# strip.net
KiCad netlist of a schematic drawn in EAGLE
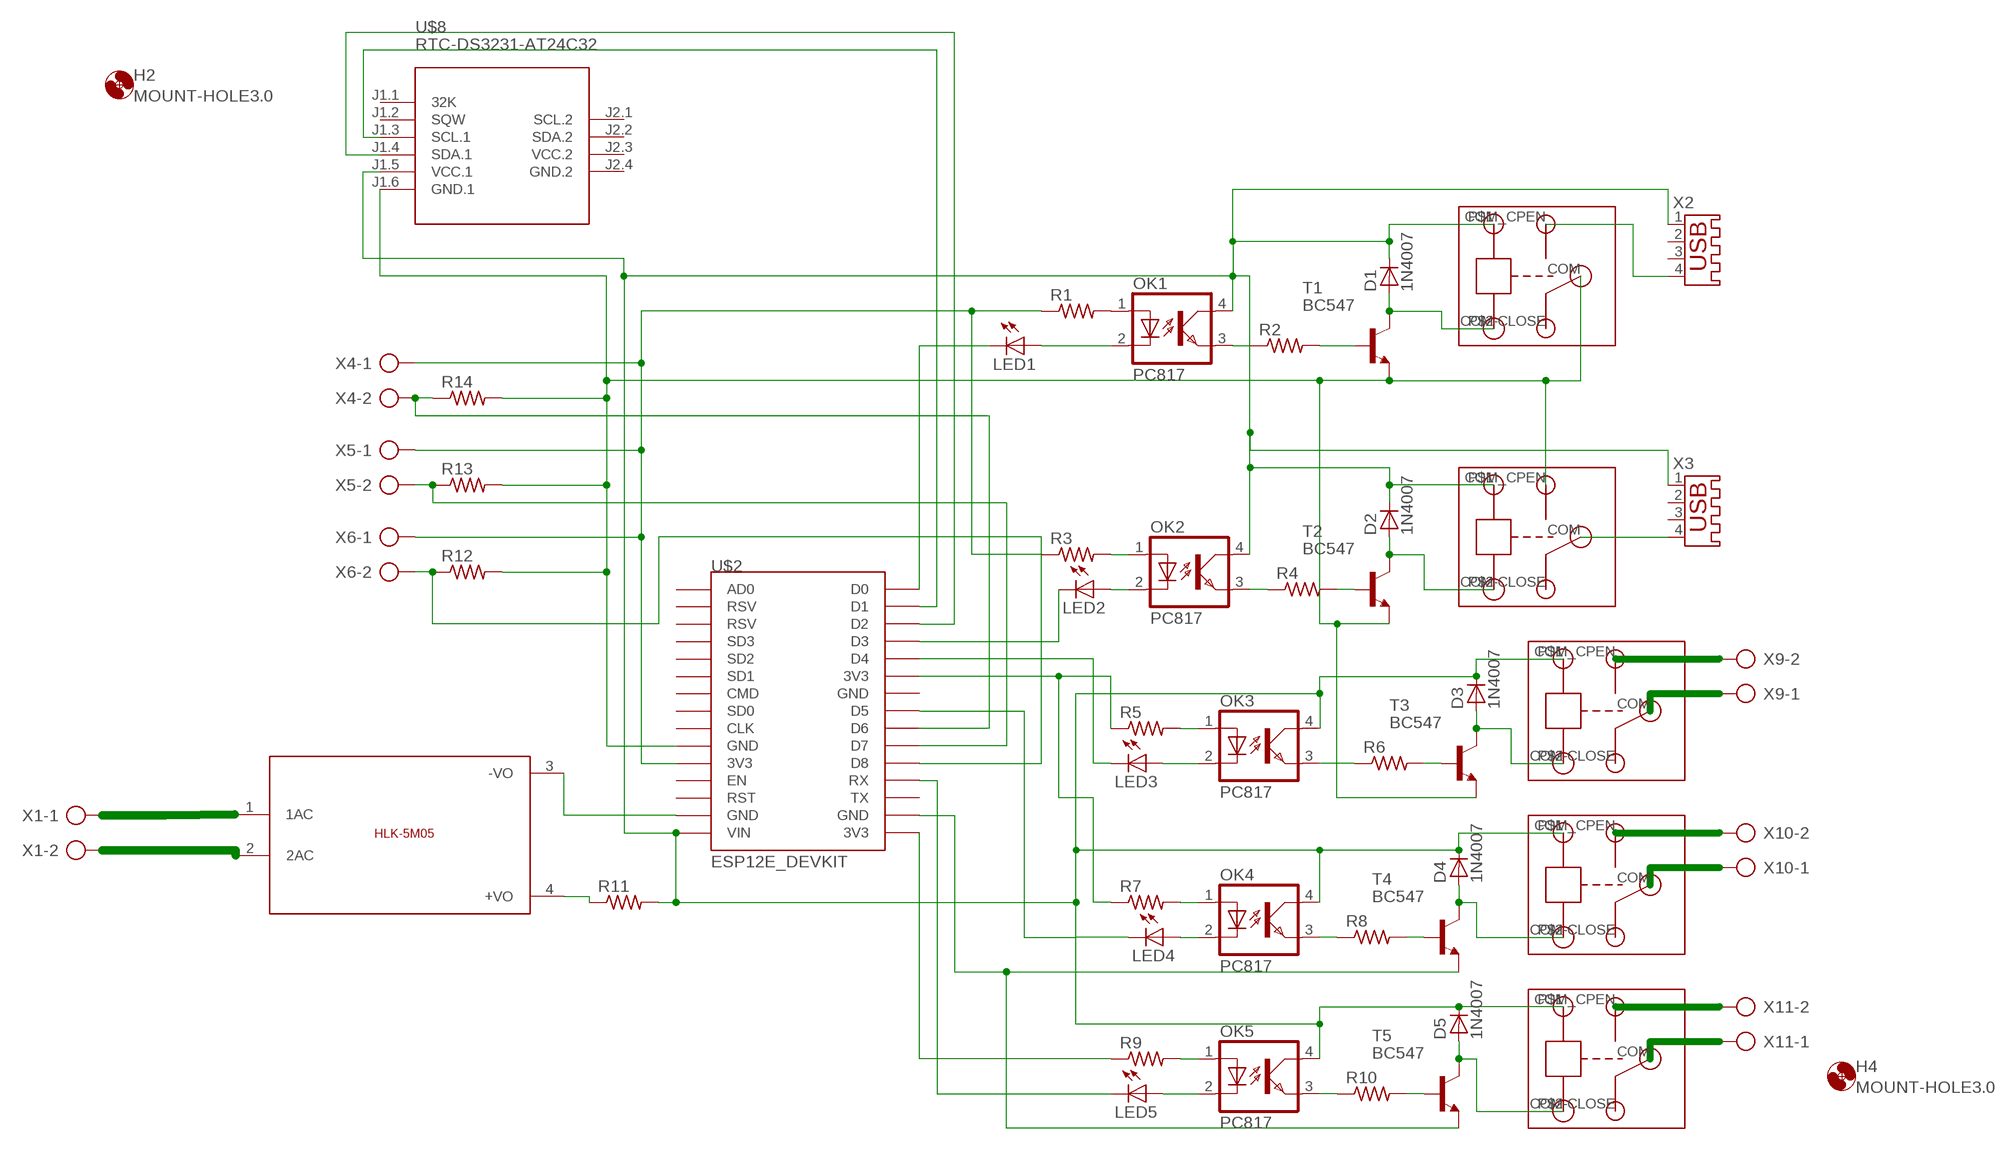
[diagram p0: schematic, sheet 1]

(export (version "E")
  (design (tool "Eeschema 10.0.6"))
  (components
    (comp (ref "D1")
      (value "1N4007")
      (footprint "eagle-import:SMA")
      (libsource (lib "eagle-import") (part "1N4007"))
    )
    (comp (ref "D2")
      (value "1N4007")
      (footprint "eagle-import:SMA")
      (libsource (lib "eagle-import") (part "1N4007"))
    )
    (comp (ref "D3")
      (value "1N4007")
      (footprint "eagle-import:SMA")
      (libsource (lib "eagle-import") (part "1N4007"))
    )
    (comp (ref "D4")
      (value "1N4007")
      (footprint "eagle-import:SMA")
      (libsource (lib "eagle-import") (part "1N4007"))
    )
    (comp (ref "D5")
      (value "1N4007")
      (footprint "eagle-import:SMA")
      (libsource (lib "eagle-import") (part "1N4007"))
    )
    (comp (ref "H2")
      (value "MOUNT-HOLE3.0")
      (footprint "eagle-import:3,0")
      (libsource (lib "eagle-import") (part "MOUNT-HOLE3.0"))
    )
    (comp (ref "H4")
      (value "MOUNT-HOLE3.0")
      (footprint "eagle-import:3,0")
      (libsource (lib "eagle-import") (part "MOUNT-HOLE3.0"))
    )
    (comp (ref "LED1")
      (value "LED3MM")
      (footprint "eagle-import:LED3MM")
      (libsource (lib "eagle-import") (part "LED3MM"))
    )
    (comp (ref "LED2")
      (value "LED3MM")
      (footprint "eagle-import:LED3MM")
      (libsource (lib "eagle-import") (part "LED3MM"))
    )
    (comp (ref "LED3")
      (value "LED3MM")
      (footprint "eagle-import:LED3MM")
      (libsource (lib "eagle-import") (part "LED3MM"))
    )
    (comp (ref "LED4")
      (value "LED3MM")
      (footprint "eagle-import:LED3MM")
      (libsource (lib "eagle-import") (part "LED3MM"))
    )
    (comp (ref "LED5")
      (value "LED3MM")
      (footprint "eagle-import:LED3MM")
      (libsource (lib "eagle-import") (part "LED3MM"))
    )
    (comp (ref "OK1")
      (value "PC817")
      (footprint "eagle-import:DIL04")
      (fields (field (name "MPN") "PC817X4J000F"))
      (libsource (lib "eagle-import") (part "PC817"))
    )
    (comp (ref "OK2")
      (value "PC817")
      (footprint "eagle-import:DIL04")
      (fields (field (name "MPN") "PC817X4J000F"))
      (libsource (lib "eagle-import") (part "PC817"))
    )
    (comp (ref "OK3")
      (value "PC817")
      (footprint "eagle-import:DIL04")
      (fields (field (name "MPN") "PC817X4J000F"))
      (libsource (lib "eagle-import") (part "PC817"))
    )
    (comp (ref "OK4")
      (value "PC817")
      (footprint "eagle-import:DIL04")
      (fields (field (name "MPN") "PC817X4J000F"))
      (libsource (lib "eagle-import") (part "PC817"))
    )
    (comp (ref "OK5")
      (value "PC817")
      (footprint "eagle-import:DIL04")
      (fields (field (name "MPN") "PC817X4J000F"))
      (libsource (lib "eagle-import") (part "PC817"))
    )
    (comp (ref "R1")
      (value "R-US_0204/5")
      (footprint "eagle-import:0204_5")
      (libsource (lib "eagle-import") (part "resistor_348_R-US_0204/5"))
    )
    (comp (ref "R2")
      (value "R-US_0204/5")
      (footprint "eagle-import:0204_5")
      (libsource (lib "eagle-import") (part "resistor_348_R-US_0204/5"))
    )
    (comp (ref "R3")
      (value "R-US_0204/5")
      (footprint "eagle-import:0204_5")
      (libsource (lib "eagle-import") (part "resistor_348_R-US_0204/5"))
    )
    (comp (ref "R4")
      (value "R-US_0204/5")
      (footprint "eagle-import:0204_5")
      (libsource (lib "eagle-import") (part "resistor_348_R-US_0204/5"))
    )
    (comp (ref "R5")
      (value "R-US_0204/5")
      (footprint "eagle-import:0204_5")
      (libsource (lib "eagle-import") (part "resistor_348_R-US_0204/5"))
    )
    (comp (ref "R6")
      (value "R-US_0204/5")
      (footprint "eagle-import:0204_5")
      (libsource (lib "eagle-import") (part "resistor_348_R-US_0204/5"))
    )
    (comp (ref "R7")
      (value "R-US_0204/5")
      (footprint "eagle-import:0204_5")
      (libsource (lib "eagle-import") (part "resistor_348_R-US_0204/5"))
    )
    (comp (ref "R8")
      (value "R-US_0204/5")
      (footprint "eagle-import:0204_5")
      (libsource (lib "eagle-import") (part "resistor_348_R-US_0204/5"))
    )
    (comp (ref "R9")
      (value "R-US_0204/5")
      (footprint "eagle-import:0204_5")
      (libsource (lib "eagle-import") (part "resistor_348_R-US_0204/5"))
    )
    (comp (ref "R10")
      (value "R-US_0204/5")
      (footprint "eagle-import:0204_5")
      (libsource (lib "eagle-import") (part "resistor_348_R-US_0204/5"))
    )
    (comp (ref "R11")
      (value "R-US_0204/5")
      (footprint "eagle-import:0204_5")
      (libsource (lib "eagle-import") (part "R-US_0204/5"))
    )
    (comp (ref "R12")
      (value "R-US_0204/5")
      (footprint "eagle-import:0204_5")
      (libsource (lib "eagle-import") (part "resistor_348_R-US_0204/5"))
    )
    (comp (ref "R13")
      (value "R-US_0204/5")
      (footprint "eagle-import:0204_5")
      (libsource (lib "eagle-import") (part "resistor_348_R-US_0204/5"))
    )
    (comp (ref "R14")
      (value "R-US_0204/5")
      (footprint "eagle-import:0204_5")
      (libsource (lib "eagle-import") (part "resistor_348_R-US_0204/5"))
    )
    (comp (ref "T1")
      (value "BC547")
      (footprint "eagle-import:TO92")
      (libsource (lib "eagle-import") (part "BC547"))
    )
    (comp (ref "T2")
      (value "BC547")
      (footprint "eagle-import:TO92")
      (libsource (lib "eagle-import") (part "BC547"))
    )
    (comp (ref "T3")
      (value "BC547")
      (footprint "eagle-import:TO92")
      (libsource (lib "eagle-import") (part "BC547"))
    )
    (comp (ref "T4")
      (value "BC547")
      (footprint "eagle-import:TO92")
      (libsource (lib "eagle-import") (part "BC547"))
    )
    (comp (ref "T5")
      (value "BC547")
      (footprint "eagle-import:TO92")
      (libsource (lib "eagle-import") (part "BC547"))
    )
    (comp (ref "U$1")
      (value "5VDC/5W")
      (footprint "eagle-import:HLK-5M05")
      (libsource (lib "eagle-import") (part "HLK-5M05"))
    )
    (comp (ref "U$2")
      (value "ESP12E_DEVKIT")
      (footprint "eagle-import:ESP12E_DEVKIT")
      (libsource (lib "eagle-import") (part "ESP12E_DEVKIT"))
    )
    (comp (ref "U$3")
      (value "RELAY")
      (footprint "eagle-import:RELAY")
      (libsource (lib "eagle-import") (part "RELAY"))
    )
    (comp (ref "U$4")
      (value "RELAY")
      (footprint "eagle-import:RELAY")
      (libsource (lib "eagle-import") (part "RELAY"))
    )
    (comp (ref "U$5")
      (value "RELAY")
      (footprint "eagle-import:RELAY")
      (libsource (lib "eagle-import") (part "RELAY"))
    )
    (comp (ref "U$6")
      (value "RELAY")
      (footprint "eagle-import:RELAY")
      (libsource (lib "eagle-import") (part "RELAY"))
    )
    (comp (ref "U$7")
      (value "RELAY")
      (footprint "eagle-import:RELAY")
      (libsource (lib "eagle-import") (part "RELAY"))
    )
    (comp (ref "U$8")
      (value "RTC-DS3231-AT24C32")
      (footprint "eagle-import:RTC-DS3231-AT24C32")
      (libsource (lib "eagle-import") (part "RTC-DS3231-AT24C32"))
    )
    (comp (ref "X1")
      (value "AK300/2")
      (footprint "eagle-import:AK300_2")
      (libsource (lib "eagle-import") (part "AK300/2"))
    )
    (comp (ref "X2")
      (value "USB-A003")
      (footprint "eagle-import:USB-A003")
      (libsource (lib "eagle-import") (part "USB-A003"))
    )
    (comp (ref "X3")
      (value "USB-A003")
      (footprint "eagle-import:USB-A003")
      (libsource (lib "eagle-import") (part "USB-A003"))
    )
    (comp (ref "X4")
      (value "AK300/2")
      (footprint "eagle-import:AK300_2")
      (libsource (lib "eagle-import") (part "AK300/2"))
    )
    (comp (ref "X5")
      (value "AK300/2")
      (footprint "eagle-import:AK300_2")
      (libsource (lib "eagle-import") (part "AK300/2"))
    )
    (comp (ref "X6")
      (value "AK300/2")
      (footprint "eagle-import:AK300_2")
      (libsource (lib "eagle-import") (part "AK300/2"))
    )
    (comp (ref "X9")
      (value "AK300/2")
      (footprint "eagle-import:AK300_2")
      (libsource (lib "eagle-import") (part "AK300/2"))
    )
    (comp (ref "X10")
      (value "AK300/2")
      (footprint "eagle-import:AK300_2")
      (libsource (lib "eagle-import") (part "AK300/2"))
    )
    (comp (ref "X11")
      (value "AK300/2")
      (footprint "eagle-import:AK300_2")
      (libsource (lib "eagle-import") (part "AK300/2"))
    )
  )
  (nets
    (net (code "1") (name "/GND.2") (class "Default")
      (node (ref "U$8") (pin "J2.4") (pinfunction "GND.2_J2.4") (pintype "power_in"))
    )
    (net (code "2") (name "/VCC.2") (class "Default")
      (node (ref "U$8") (pin "J2.3") (pinfunction "VCC.2_J2.3") (pintype "power_in"))
    )
    (net (code "3") (name "Net-(D1-C)") (class "Default")
      (node (ref "D1") (pin "K") (pinfunction "C_K") (pintype "passive"))
      (node (ref "D2") (pin "K") (pinfunction "C_K") (pintype "passive"))
      (node (ref "D3") (pin "K") (pinfunction "C_K") (pintype "passive"))
      (node (ref "D4") (pin "K") (pinfunction "C_K") (pintype "passive"))
      (node (ref "D5") (pin "K") (pinfunction "C_K") (pintype "passive"))
      (node (ref "OK1") (pin "4") (pinfunction "COL_4") (pintype "passive"))
      (node (ref "OK2") (pin "4") (pinfunction "COL_4") (pintype "passive"))
      (node (ref "OK3") (pin "4") (pinfunction "COL_4") (pintype "passive"))
      (node (ref "OK4") (pin "4") (pinfunction "COL_4") (pintype "passive"))
      (node (ref "OK5") (pin "4") (pinfunction "COL_4") (pintype "passive"))
      (node (ref "R11") (pin "2") (pinfunction "2_2") (pintype "passive"))
      (node (ref "U$2") (pin "VIN") (pinfunction "VIN_VIN") (pintype "bidirectional"))
      (node (ref "U$3") (pin "P$1") (pinfunction "IN_P$1") (pintype "bidirectional"))
      (node (ref "U$4") (pin "P$1") (pinfunction "IN_P$1") (pintype "bidirectional"))
      (node (ref "U$5") (pin "P$1") (pinfunction "IN_P$1") (pintype "bidirectional"))
      (node (ref "U$6") (pin "P$1") (pinfunction "IN_P$1") (pintype "bidirectional"))
      (node (ref "U$7") (pin "P$1") (pinfunction "IN_P$1") (pintype "bidirectional"))
      (node (ref "U$8") (pin "J1.5") (pinfunction "VCC.1_J1.5") (pintype "power_in"))
      (node (ref "X2") (pin "1") (pinfunction "1_1") (pintype "passive"))
      (node (ref "X3") (pin "1") (pinfunction "1_1") (pintype "passive"))
    )
    (net (code "4") (name "Net-(LED1-C)") (class "Default")
      (node (ref "LED1") (pin "K") (pinfunction "C_K") (pintype "passive"))
      (node (ref "U$2") (pin "D0") (pinfunction "D0_D0") (pintype "bidirectional"))
    )
    (net (code "5") (name "Net-(LED2-C)") (class "Default")
      (node (ref "LED2") (pin "K") (pinfunction "C_K") (pintype "passive"))
      (node (ref "U$2") (pin "D3") (pinfunction "D3_D3") (pintype "bidirectional"))
    )
    (net (code "6") (name "Net-(LED3-C)") (class "Default")
      (node (ref "LED3") (pin "K") (pinfunction "C_K") (pintype "passive"))
      (node (ref "U$2") (pin "D4") (pinfunction "D4_D4") (pintype "bidirectional"))
    )
    (net (code "7") (name "Net-(LED4-C)") (class "Default")
      (node (ref "LED4") (pin "K") (pinfunction "C_K") (pintype "passive"))
      (node (ref "U$2") (pin "D5") (pinfunction "D5_D5") (pintype "bidirectional"))
    )
    (net (code "8") (name "Net-(LED5-C)") (class "Default")
      (node (ref "LED5") (pin "K") (pinfunction "C_K") (pintype "passive"))
      (node (ref "U$2") (pin "RX") (pinfunction "RX_RX") (pintype "bidirectional"))
    )
    (net (code "9") (name "Net-(OK1-A)") (class "Default")
      (node (ref "OK1") (pin "1") (pinfunction "A_1") (pintype "passive"))
      (node (ref "R1") (pin "2") (pinfunction "2_2") (pintype "passive"))
    )
    (net (code "10") (name "Net-(OK1-C)") (class "Default")
      (node (ref "LED1") (pin "A") (pinfunction "A_A") (pintype "passive"))
      (node (ref "OK1") (pin "2") (pinfunction "C_2") (pintype "passive"))
    )
    (net (code "11") (name "Net-(OK1-EMIT)") (class "Default")
      (node (ref "OK1") (pin "3") (pinfunction "EMIT_3") (pintype "passive"))
      (node (ref "R2") (pin "1") (pinfunction "1_1") (pintype "passive"))
    )
    (net (code "12") (name "Net-(OK2-A)") (class "Default")
      (node (ref "OK2") (pin "1") (pinfunction "A_1") (pintype "passive"))
      (node (ref "R3") (pin "2") (pinfunction "2_2") (pintype "passive"))
    )
    (net (code "13") (name "Net-(OK2-C)") (class "Default")
      (node (ref "LED2") (pin "A") (pinfunction "A_A") (pintype "passive"))
      (node (ref "OK2") (pin "2") (pinfunction "C_2") (pintype "passive"))
    )
    (net (code "14") (name "Net-(OK2-EMIT)") (class "Default")
      (node (ref "OK2") (pin "3") (pinfunction "EMIT_3") (pintype "passive"))
      (node (ref "R4") (pin "1") (pinfunction "1_1") (pintype "passive"))
    )
    (net (code "15") (name "Net-(OK3-A)") (class "Default")
      (node (ref "OK3") (pin "1") (pinfunction "A_1") (pintype "passive"))
      (node (ref "R5") (pin "2") (pinfunction "2_2") (pintype "passive"))
    )
    (net (code "16") (name "Net-(OK3-C)") (class "Default")
      (node (ref "LED3") (pin "A") (pinfunction "A_A") (pintype "passive"))
      (node (ref "OK3") (pin "2") (pinfunction "C_2") (pintype "passive"))
    )
    (net (code "17") (name "Net-(OK3-EMIT)") (class "Default")
      (node (ref "OK3") (pin "3") (pinfunction "EMIT_3") (pintype "passive"))
      (node (ref "R6") (pin "1") (pinfunction "1_1") (pintype "passive"))
    )
    (net (code "18") (name "Net-(OK4-A)") (class "Default")
      (node (ref "OK4") (pin "1") (pinfunction "A_1") (pintype "passive"))
      (node (ref "R7") (pin "2") (pinfunction "2_2") (pintype "passive"))
    )
    (net (code "19") (name "Net-(OK4-C)") (class "Default")
      (node (ref "LED4") (pin "A") (pinfunction "A_A") (pintype "passive"))
      (node (ref "OK4") (pin "2") (pinfunction "C_2") (pintype "passive"))
    )
    (net (code "20") (name "Net-(OK4-EMIT)") (class "Default")
      (node (ref "OK4") (pin "3") (pinfunction "EMIT_3") (pintype "passive"))
      (node (ref "R8") (pin "1") (pinfunction "1_1") (pintype "passive"))
    )
    (net (code "21") (name "Net-(OK5-A)") (class "Default")
      (node (ref "OK5") (pin "1") (pinfunction "A_1") (pintype "passive"))
      (node (ref "R9") (pin "2") (pinfunction "2_2") (pintype "passive"))
    )
    (net (code "22") (name "Net-(OK5-C)") (class "Default")
      (node (ref "LED5") (pin "A") (pinfunction "A_A") (pintype "passive"))
      (node (ref "OK5") (pin "2") (pinfunction "C_2") (pintype "passive"))
    )
    (net (code "23") (name "Net-(OK5-EMIT)") (class "Default")
      (node (ref "OK5") (pin "3") (pinfunction "EMIT_3") (pintype "passive"))
      (node (ref "R10") (pin "1") (pinfunction "1_1") (pintype "passive"))
    )
    (net (code "24") (name "Net-(R5-Pad1)") (class "Default")
      (node (ref "R5") (pin "1") (pinfunction "1_1") (pintype "passive"))
      (node (ref "R7") (pin "1") (pinfunction "1_1") (pintype "passive"))
      (node (ref "U$2") (pin "3V3@1") (pinfunction "3V3_3V3@1") (pintype "bidirectional"))
    )
    (net (code "25") (name "Net-(R9-Pad1)") (class "Default")
      (node (ref "R9") (pin "1") (pinfunction "1_1") (pintype "passive"))
      (node (ref "U$2") (pin "3V3@2") (pinfunction "3V3_3V3@2") (pintype "bidirectional"))
    )
    (net (code "26") (name "Net-(T1-B)") (class "Default")
      (node (ref "R2") (pin "2") (pinfunction "2_2") (pintype "passive"))
      (node (ref "T1") (pin "2") (pinfunction "B_2") (pintype "passive"))
    )
    (net (code "27") (name "Net-(T1-C)") (class "Default")
      (node (ref "D1") (pin "A") (pinfunction "A_A") (pintype "passive"))
      (node (ref "T1") (pin "3") (pinfunction "C_3") (pintype "passive"))
      (node (ref "U$3") (pin "P$2") (pinfunction "GND_P$2") (pintype "bidirectional"))
    )
    (net (code "28") (name "Net-(T1-E)") (class "Default")
      (node (ref "R12") (pin "2") (pinfunction "2_2") (pintype "passive"))
      (node (ref "R13") (pin "2") (pinfunction "2_2") (pintype "passive"))
      (node (ref "R14") (pin "2") (pinfunction "2_2") (pintype "passive"))
      (node (ref "T1") (pin "1") (pinfunction "E_1") (pintype "passive"))
      (node (ref "T2") (pin "1") (pinfunction "E_1") (pintype "passive"))
      (node (ref "T3") (pin "1") (pinfunction "E_1") (pintype "passive"))
      (node (ref "U$2") (pin "GND@0") (pinfunction "GND_GND@0") (pintype "bidirectional"))
      (node (ref "U$3") (pin "COM") (pinfunction "COM_COM") (pintype "bidirectional"))
      (node (ref "U$4") (pin "COM_CPEN") (pinfunction "COM-OPEN_COM_CPEN") (pintype "bidirectional"))
      (node (ref "U$8") (pin "J1.6") (pinfunction "GND.1_J1.6") (pintype "power_in"))
    )
    (net (code "29") (name "Net-(T2-B)") (class "Default")
      (node (ref "R4") (pin "2") (pinfunction "2_2") (pintype "passive"))
      (node (ref "T2") (pin "2") (pinfunction "B_2") (pintype "passive"))
    )
    (net (code "30") (name "Net-(T2-C)") (class "Default")
      (node (ref "D2") (pin "A") (pinfunction "A_A") (pintype "passive"))
      (node (ref "T2") (pin "3") (pinfunction "C_3") (pintype "passive"))
      (node (ref "U$4") (pin "P$2") (pinfunction "GND_P$2") (pintype "bidirectional"))
    )
    (net (code "31") (name "Net-(T3-B)") (class "Default")
      (node (ref "R6") (pin "2") (pinfunction "2_2") (pintype "passive"))
      (node (ref "T3") (pin "2") (pinfunction "B_2") (pintype "passive"))
    )
    (net (code "32") (name "Net-(T3-C)") (class "Default")
      (node (ref "D3") (pin "A") (pinfunction "A_A") (pintype "passive"))
      (node (ref "T3") (pin "3") (pinfunction "C_3") (pintype "passive"))
      (node (ref "U$5") (pin "P$2") (pinfunction "GND_P$2") (pintype "bidirectional"))
    )
    (net (code "33") (name "Net-(T4-B)") (class "Default")
      (node (ref "R8") (pin "2") (pinfunction "2_2") (pintype "passive"))
      (node (ref "T4") (pin "2") (pinfunction "B_2") (pintype "passive"))
    )
    (net (code "34") (name "Net-(T4-C)") (class "Default")
      (node (ref "D4") (pin "A") (pinfunction "A_A") (pintype "passive"))
      (node (ref "T4") (pin "3") (pinfunction "C_3") (pintype "passive"))
      (node (ref "U$6") (pin "P$2") (pinfunction "GND_P$2") (pintype "bidirectional"))
    )
    (net (code "35") (name "Net-(T4-E)") (class "Default")
      (node (ref "T4") (pin "1") (pinfunction "E_1") (pintype "passive"))
      (node (ref "T5") (pin "1") (pinfunction "E_1") (pintype "passive"))
      (node (ref "U$2") (pin "GND@3") (pinfunction "GND_GND@3") (pintype "bidirectional"))
    )
    (net (code "36") (name "Net-(T5-B)") (class "Default")
      (node (ref "R10") (pin "2") (pinfunction "2_2") (pintype "passive"))
      (node (ref "T5") (pin "2") (pinfunction "B_2") (pintype "passive"))
    )
    (net (code "37") (name "Net-(T5-C)") (class "Default")
      (node (ref "D5") (pin "A") (pinfunction "A_A") (pintype "passive"))
      (node (ref "T5") (pin "3") (pinfunction "C_3") (pintype "passive"))
      (node (ref "U$7") (pin "P$2") (pinfunction "GND_P$2") (pintype "bidirectional"))
    )
    (net (code "38") (name "Net-(U$1-+VO)") (class "Default")
      (node (ref "R11") (pin "1") (pinfunction "1_1") (pintype "passive"))
      (node (ref "U$1") (pin "4") (pinfunction "+VO_4") (pintype "bidirectional"))
    )
    (net (code "39") (name "Net-(U$1--VO)") (class "Default")
      (node (ref "U$1") (pin "3") (pinfunction "-VO_3") (pintype "bidirectional"))
      (node (ref "U$2") (pin "GND@1") (pinfunction "GND_GND@1") (pintype "bidirectional"))
    )
    (net (code "40") (name "Net-(U$1-1AC)") (class "Default")
      (node (ref "U$1") (pin "1") (pinfunction "1AC_1") (pintype "bidirectional"))
      (node (ref "X1") (pin "1") (pinfunction "KL_1") (pintype "passive"))
    )
    (net (code "41") (name "Net-(U$1-2AC)") (class "Default")
      (node (ref "U$1") (pin "2") (pinfunction "2AC_2") (pintype "bidirectional"))
      (node (ref "X1") (pin "2") (pinfunction "KL_2") (pintype "passive"))
    )
    (net (code "42") (name "Net-(U$3-COM-OPEN)") (class "Default")
      (node (ref "U$3") (pin "COM_CPEN") (pinfunction "COM-OPEN_COM_CPEN") (pintype "bidirectional"))
      (node (ref "X2") (pin "4") (pinfunction "4_4") (pintype "passive"))
    )
    (net (code "43") (name "Net-(U$4-PadCOM)") (class "Default")
      (node (ref "U$4") (pin "COM") (pinfunction "COM_COM") (pintype "bidirectional"))
      (node (ref "X3") (pin "4") (pinfunction "4_4") (pintype "passive"))
    )
    (net (code "44") (name "Net-(U$5-COM-OPEN)") (class "Default")
      (node (ref "U$5") (pin "COM_CPEN") (pinfunction "COM-OPEN_COM_CPEN") (pintype "bidirectional"))
      (node (ref "X9") (pin "2") (pinfunction "KL_2") (pintype "passive"))
    )
    (net (code "45") (name "Net-(U$6-COM-OPEN)") (class "Default")
      (node (ref "U$6") (pin "COM_CPEN") (pinfunction "COM-OPEN_COM_CPEN") (pintype "bidirectional"))
      (node (ref "X10") (pin "2") (pinfunction "KL_2") (pintype "passive"))
    )
    (net (code "46") (name "Net-(U$7-COM-OPEN)") (class "Default")
      (node (ref "U$7") (pin "COM_CPEN") (pinfunction "COM-OPEN_COM_CPEN") (pintype "bidirectional"))
      (node (ref "X11") (pin "2") (pinfunction "KL_2") (pintype "passive"))
    )
    (net (code "47") (name "Net-(U$8-SCL.1)") (class "Default")
      (node (ref "U$2") (pin "D1") (pinfunction "D1_D1") (pintype "bidirectional"))
      (node (ref "U$8") (pin "J1.3") (pinfunction "SCL.1_J1.3") (pintype "bidirectional"))
    )
    (net (code "48") (name "Net-(U$8-SDA.1)") (class "Default")
      (node (ref "U$2") (pin "D2") (pinfunction "D2_D2") (pintype "bidirectional"))
      (node (ref "U$8") (pin "J1.4") (pinfunction "SDA.1_J1.4") (pintype "bidirectional"))
    )
    (net (code "49") (name "Net-(X4A-KL)") (class "Default")
      (node (ref "R1") (pin "1") (pinfunction "1_1") (pintype "passive"))
      (node (ref "R3") (pin "1") (pinfunction "1_1") (pintype "passive"))
      (node (ref "U$2") (pin "3V3@0") (pinfunction "3V3_3V3@0") (pintype "bidirectional"))
      (node (ref "X4") (pin "1") (pinfunction "KL_1") (pintype "passive"))
      (node (ref "X5") (pin "1") (pinfunction "KL_1") (pintype "passive"))
      (node (ref "X6") (pin "1") (pinfunction "KL_1") (pintype "passive"))
    )
    (net (code "50") (name "Net-(X4B-KL)") (class "Default")
      (node (ref "R14") (pin "1") (pinfunction "1_1") (pintype "passive"))
      (node (ref "U$2") (pin "D6") (pinfunction "D6_D6") (pintype "bidirectional"))
      (node (ref "X4") (pin "2") (pinfunction "KL_2") (pintype "passive"))
    )
    (net (code "51") (name "Net-(X5B-KL)") (class "Default")
      (node (ref "R13") (pin "1") (pinfunction "1_1") (pintype "passive"))
      (node (ref "U$2") (pin "D7") (pinfunction "D7_D7") (pintype "bidirectional"))
      (node (ref "X5") (pin "2") (pinfunction "KL_2") (pintype "passive"))
    )
    (net (code "52") (name "Net-(X6B-KL)") (class "Default")
      (node (ref "R12") (pin "1") (pinfunction "1_1") (pintype "passive"))
      (node (ref "U$2") (pin "D8") (pinfunction "D8_D8") (pintype "bidirectional"))
      (node (ref "X6") (pin "2") (pinfunction "KL_2") (pintype "passive"))
    )
    (net (code "53") (name "Net-(X9A-KL)") (class "Default")
      (node (ref "U$5") (pin "COM") (pinfunction "COM_COM") (pintype "bidirectional"))
      (node (ref "X9") (pin "1") (pinfunction "KL_1") (pintype "passive"))
    )
    (net (code "54") (name "Net-(X10A-KL)") (class "Default")
      (node (ref "U$6") (pin "COM") (pinfunction "COM_COM") (pintype "bidirectional"))
      (node (ref "X10") (pin "1") (pinfunction "KL_1") (pintype "passive"))
    )
    (net (code "55") (name "Net-(X11A-KL)") (class "Default")
      (node (ref "U$7") (pin "COM") (pinfunction "COM_COM") (pintype "bidirectional"))
      (node (ref "X11") (pin "1") (pinfunction "KL_1") (pintype "passive"))
    )
    (net (code "56") (name "unconnected-(U$2-GND-PadGND@2)") (class "Default")
      (node (ref "U$2") (pin "GND@2") (pinfunction "GND_GND@2") (pintype "bidirectional"))
    )
    (net (code "57") (name "unconnected-(U$2-PadAD0)") (class "Default")
      (node (ref "U$2") (pin "AD0") (pinfunction "AD0_AD0") (pintype "bidirectional"))
    )
    (net (code "58") (name "unconnected-(U$2-PadCLK)") (class "Default")
      (node (ref "U$2") (pin "CLK") (pinfunction "CLK_CLK") (pintype "bidirectional"))
    )
    (net (code "59") (name "unconnected-(U$2-PadCMD)") (class "Default")
      (node (ref "U$2") (pin "CMD") (pinfunction "CMD_CMD") (pintype "bidirectional"))
    )
    (net (code "60") (name "unconnected-(U$2-PadEN)") (class "Default")
      (node (ref "U$2") (pin "EN") (pinfunction "EN_EN") (pintype "bidirectional"))
    )
    (net (code "61") (name "unconnected-(U$2-PadRST)") (class "Default")
      (node (ref "U$2") (pin "RST") (pinfunction "RST_RST") (pintype "bidirectional"))
    )
    (net (code "62") (name "unconnected-(U$2-PadSD0)") (class "Default")
      (node (ref "U$2") (pin "SD0") (pinfunction "SD0_SD0") (pintype "bidirectional"))
    )
    (net (code "63") (name "unconnected-(U$2-PadSD1)") (class "Default")
      (node (ref "U$2") (pin "SD1") (pinfunction "SD1_SD1") (pintype "bidirectional"))
    )
    (net (code "64") (name "unconnected-(U$2-PadSD2)") (class "Default")
      (node (ref "U$2") (pin "SD2") (pinfunction "SD2_SD2") (pintype "bidirectional"))
    )
    (net (code "65") (name "unconnected-(U$2-PadSD3)") (class "Default")
      (node (ref "U$2") (pin "SD3") (pinfunction "SD3_SD3") (pintype "bidirectional"))
    )
    (net (code "66") (name "unconnected-(U$2-PadTX)") (class "Default")
      (node (ref "U$2") (pin "TX") (pinfunction "TX_TX") (pintype "bidirectional"))
    )
    (net (code "67") (name "unconnected-(U$2-RSV-PadRSV@0)") (class "Default")
      (node (ref "U$2") (pin "RSV@0") (pinfunction "RSV_RSV@0") (pintype "bidirectional"))
    )
    (net (code "68") (name "unconnected-(U$2-RSV-PadRSV@1)") (class "Default")
      (node (ref "U$2") (pin "RSV@1") (pinfunction "RSV_RSV@1") (pintype "bidirectional"))
    )
    (net (code "69") (name "unconnected-(U$3-PadCOM-CLOSE)") (class "Default")
      (node (ref "U$3") (pin "COM-CLOSE") (pinfunction "COM-CLOSE_COM-CLOSE") (pintype "bidirectional"))
    )
    (net (code "70") (name "unconnected-(U$4-PadCOM-CLOSE)") (class "Default")
      (node (ref "U$4") (pin "COM-CLOSE") (pinfunction "COM-CLOSE_COM-CLOSE") (pintype "bidirectional"))
    )
    (net (code "71") (name "unconnected-(U$5-PadCOM-CLOSE)") (class "Default")
      (node (ref "U$5") (pin "COM-CLOSE") (pinfunction "COM-CLOSE_COM-CLOSE") (pintype "bidirectional"))
    )
    (net (code "72") (name "unconnected-(U$6-PadCOM-CLOSE)") (class "Default")
      (node (ref "U$6") (pin "COM-CLOSE") (pinfunction "COM-CLOSE_COM-CLOSE") (pintype "bidirectional"))
    )
    (net (code "73") (name "unconnected-(U$7-PadCOM-CLOSE)") (class "Default")
      (node (ref "U$7") (pin "COM-CLOSE") (pinfunction "COM-CLOSE_COM-CLOSE") (pintype "bidirectional"))
    )
    (net (code "74") (name "unconnected-(U$8-32K-PadJ1.1)") (class "Default")
      (node (ref "U$8") (pin "J1.1") (pinfunction "32K_J1.1") (pintype "bidirectional"))
    )
    (net (code "75") (name "unconnected-(U$8-SCL.2-PadJ2.1)") (class "Default")
      (node (ref "U$8") (pin "J2.1") (pinfunction "SCL.2_J2.1") (pintype "bidirectional"))
    )
    (net (code "76") (name "unconnected-(U$8-SDA.2-PadJ2.2)") (class "Default")
      (node (ref "U$8") (pin "J2.2") (pinfunction "SDA.2_J2.2") (pintype "bidirectional"))
    )
    (net (code "77") (name "unconnected-(U$8-SQW-PadJ1.2)") (class "Default")
      (node (ref "U$8") (pin "J1.2") (pinfunction "SQW_J1.2") (pintype "bidirectional"))
    )
    (net (code "78") (name "unconnected-(X2-Pad2)") (class "Default")
      (node (ref "X2") (pin "2") (pinfunction "2_2") (pintype "passive"))
    )
    (net (code "79") (name "unconnected-(X2-Pad3)") (class "Default")
      (node (ref "X2") (pin "3") (pinfunction "3_3") (pintype "passive"))
    )
    (net (code "80") (name "unconnected-(X3-Pad2)") (class "Default")
      (node (ref "X3") (pin "2") (pinfunction "2_2") (pintype "passive"))
    )
    (net (code "81") (name "unconnected-(X3-Pad3)") (class "Default")
      (node (ref "X3") (pin "3") (pinfunction "3_3") (pintype "passive"))
    )
  )
)
